# sauroneye.net
KiCad netlist of a schematic drawn in EAGLE
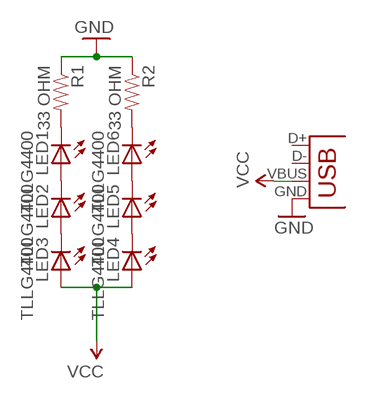
[diagram p0: schematic, sheet 1]

(export (version "E")
  (design (tool "Eeschema 10.0.6"))
  (components
    (comp (ref "LED1")
      (value "TLLG4400")
      (footprint "eagle-import:LED3MM")
      (fields (field (name "MF") "VISHAY SEMICONDUCTOR"))
      (libsource (lib "eagle-import") (part "TLLG4400"))
    )
    (comp (ref "LED2")
      (value "TLLG4400")
      (footprint "eagle-import:LED3MM")
      (fields (field (name "MF") "VISHAY SEMICONDUCTOR"))
      (libsource (lib "eagle-import") (part "TLLG4400"))
    )
    (comp (ref "LED3")
      (value "TLLG4400")
      (footprint "eagle-import:LED3MM")
      (fields (field (name "MF") "VISHAY SEMICONDUCTOR"))
      (libsource (lib "eagle-import") (part "TLLG4400"))
    )
    (comp (ref "LED4")
      (value "TLLG4400")
      (footprint "eagle-import:LED3MM")
      (fields (field (name "MF") "VISHAY SEMICONDUCTOR"))
      (libsource (lib "eagle-import") (part "TLLG4400"))
    )
    (comp (ref "LED5")
      (value "TLLG4400")
      (footprint "eagle-import:LED3MM")
      (fields (field (name "MF") "VISHAY SEMICONDUCTOR"))
      (libsource (lib "eagle-import") (part "TLLG4400"))
    )
    (comp (ref "LED6")
      (value "TLLG4400")
      (footprint "eagle-import:LED3MM")
      (fields (field (name "MF") "VISHAY SEMICONDUCTOR"))
      (libsource (lib "eagle-import") (part "TLLG4400"))
    )
    (comp (ref "R1")
      (value "33 OHM")
      (footprint "eagle-import:AXIAL-0.3")
      (libsource (lib "eagle-import") (part "RESISTORAXIAL-0.3"))
    )
    (comp (ref "R2")
      (value "33 OHM")
      (footprint "eagle-import:AXIAL-0.3")
      (libsource (lib "eagle-import") (part "RESISTORAXIAL-0.3"))
    )
    (comp (ref "X1")
      (value "USBSMD")
      (footprint "eagle-import:USB-MINIB")
      (libsource (lib "eagle-import") (part "USBSMD"))
    )
  )
  (nets
    (net (code "1") (name "GND") (class "Default")
      (node (ref "R1") (pin "P$1") (pinfunction "1_P$1") (pintype "passive"))
      (node (ref "R2") (pin "P$1") (pinfunction "1_P$1") (pintype "passive"))
      (node (ref "X1") (pin "GND") (pinfunction "GND_GND") (pintype "bidirectional"))
    )
    (net (code "2") (name "Net-(LED1-C)") (class "Default")
      (node (ref "LED1") (pin "K") (pinfunction "C_K") (pintype "passive"))
      (node (ref "R1") (pin "P$2") (pinfunction "2_P$2") (pintype "passive"))
    )
    (net (code "3") (name "Net-(LED2-C)") (class "Default")
      (node (ref "LED1") (pin "A") (pinfunction "A_A") (pintype "passive"))
      (node (ref "LED2") (pin "K") (pinfunction "C_K") (pintype "passive"))
    )
    (net (code "4") (name "Net-(LED3-C)") (class "Default")
      (node (ref "LED2") (pin "A") (pinfunction "A_A") (pintype "passive"))
      (node (ref "LED3") (pin "K") (pinfunction "C_K") (pintype "passive"))
    )
    (net (code "5") (name "Net-(LED4-C)") (class "Default")
      (node (ref "LED4") (pin "K") (pinfunction "C_K") (pintype "passive"))
      (node (ref "LED5") (pin "A") (pinfunction "A_A") (pintype "passive"))
    )
    (net (code "6") (name "Net-(LED5-C)") (class "Default")
      (node (ref "LED5") (pin "K") (pinfunction "C_K") (pintype "passive"))
      (node (ref "LED6") (pin "A") (pinfunction "A_A") (pintype "passive"))
    )
    (net (code "7") (name "Net-(LED6-C)") (class "Default")
      (node (ref "LED6") (pin "K") (pinfunction "C_K") (pintype "passive"))
      (node (ref "R2") (pin "P$2") (pinfunction "2_P$2") (pintype "passive"))
    )
    (net (code "8") (name "VCC") (class "Default")
      (node (ref "LED3") (pin "A") (pinfunction "A_A") (pintype "passive"))
      (node (ref "LED4") (pin "A") (pinfunction "A_A") (pintype "passive"))
      (node (ref "X1") (pin "VBUS") (pinfunction "VBUS_VBUS") (pintype "bidirectional"))
    )
    (net (code "9") (name "unconnected-(X1-PadD+)") (class "Default")
      (node (ref "X1") (pin "D+") (pinfunction "D+_D+") (pintype "bidirectional"))
    )
    (net (code "10") (name "unconnected-(X1-PadD-)") (class "Default")
      (node (ref "X1") (pin "D-") (pinfunction "D-_D-") (pintype "bidirectional"))
    )
  )
)
